# SFP_PortA-B.net
KiCad netlist of a schematic drawn in Altium Designer
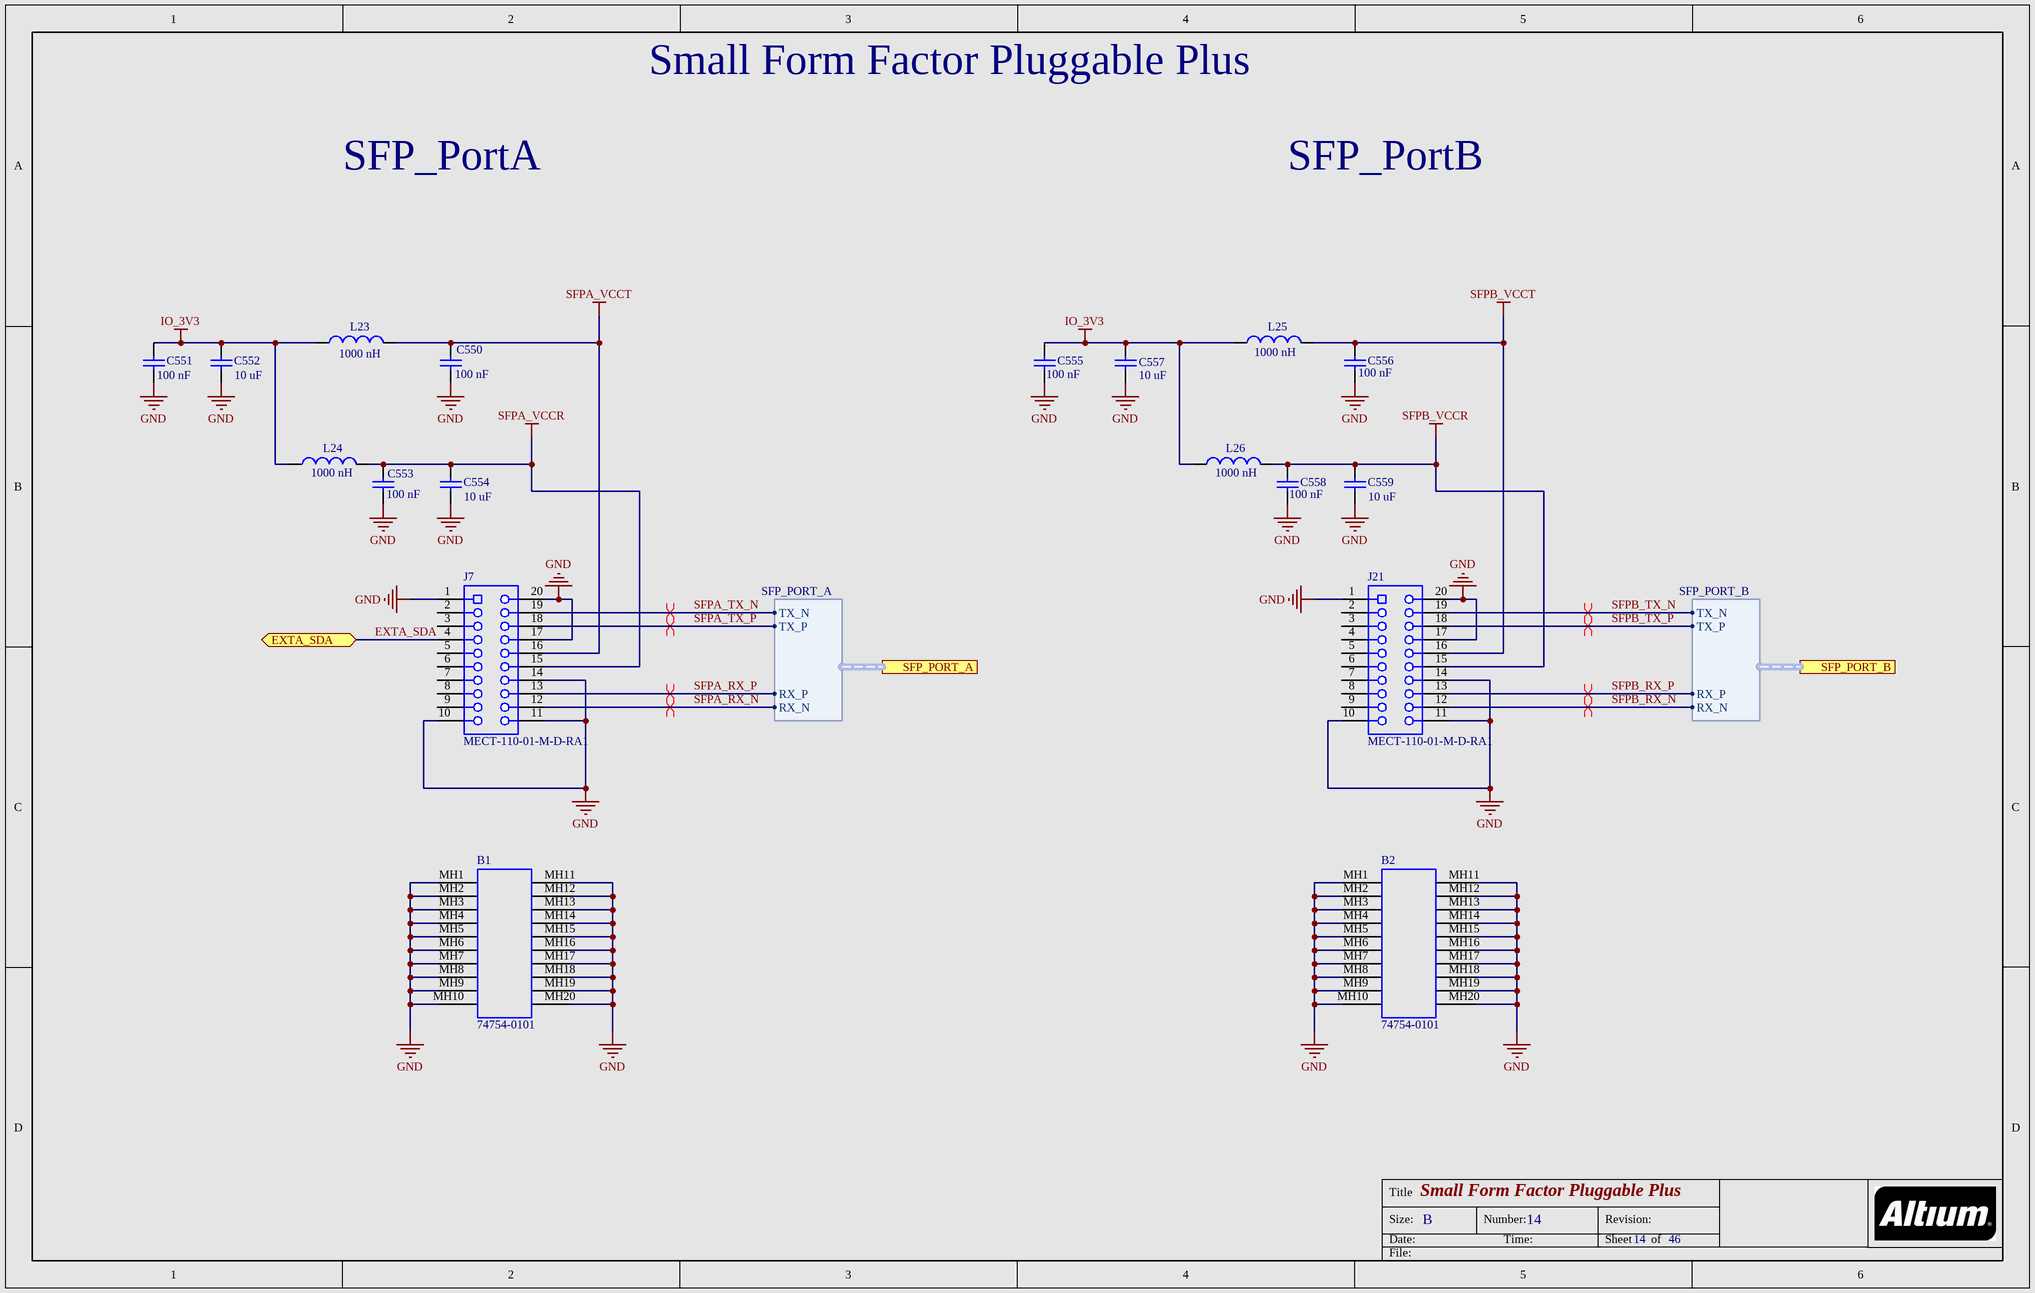
[diagram p0:  SFP_PortA-B.SchDoc]

(export (version "E")
  (design (tool "Eeschema 10.0.6"))
  (components
    (comp (ref "B1")
      (value "74754-0101")
      (footprint "MOLX-74754-0101_V")
      (description "SFP+ Cage, Single Port, Height 10.85 mm, Tail Height 3.05 mm, -40 to 85 degC, RoHS, Tray")
      (fields (field (name "MANUFACTURER") "Molex"))
      (libsource (lib "Altium Content Vault") (part "MOLX-74754-0101"))
    )
    (comp (ref "B2")
      (value "74754-0101")
      (footprint "MOLX-74754-0101_V")
      (description "SFP+ Cage, Single Port, Height 10.85 mm, Tail Height 3.05 mm, -40 to 85 degC, RoHS, Tray")
      (fields (field (name "MANUFACTURER") "Molex"))
      (libsource (lib "Altium Content Vault") (part "MOLX-74754-0101"))
    )
    (comp (ref "C550")
      (value "C1005X7R1E104M")
      (footprint "CAPC1005X55X10LL05")
      (description "Chip Capacitor, 0.1 uF, +/- 20%, 25 V, -55 to 125 degC, 0402 (1005 Metric), RoHS, Tape and Reel")
      (fields (field (name "TOLERANCE") "20%") (field (name "CAPACITANCE") "100 nF"))
      (libsource (lib "Altium Content Vault") (part "CAP-NP-2"))
    )
    (comp (ref "C551")
      (value "C1005X7R1E104M")
      (footprint "CAPC1005X55X10LL05")
      (description "Chip Capacitor, 0.1 uF, +/- 20%, 25 V, -55 to 125 degC, 0402 (1005 Metric), RoHS, Tape and Reel")
      (fields (field (name "TOLERANCE") "20%") (field (name "CAPACITANCE") "100 nF"))
      (libsource (lib "Altium Content Vault") (part "CAP-NP-2"))
    )
    (comp (ref "C552")
      (value "C2012X5R1C106K085AC")
      (footprint "CAPC2013X100X20NL20")
      (description "Chip Capacitor, 10 uF, +/- 10%, 16 V, -55 to 85 degC, 0805 (2012 Metric), RoHS, Tape and Reel")
      (fields (field (name "TOLERANCE") "10%") (field (name "CAPACITANCE") "10 uF"))
      (libsource (lib "Altium Content Vault") (part "CMP-1663-00007-1"))
    )
    (comp (ref "C553")
      (value "C1005X7R1E104M")
      (footprint "CAPC1005X55X10LL05")
      (description "Chip Capacitor, 0.1 uF, +/- 20%, 25 V, -55 to 125 degC, 0402 (1005 Metric), RoHS, Tape and Reel")
      (fields (field (name "TOLERANCE") "20%") (field (name "CAPACITANCE") "100 nF"))
      (libsource (lib "Altium Content Vault") (part "CAP-NP-2"))
    )
    (comp (ref "C554")
      (value "C2012X5R1C106K085AC")
      (footprint "CAPC2013X100X20NL20")
      (description "Chip Capacitor, 10 uF, +/- 10%, 16 V, -55 to 85 degC, 0805 (2012 Metric), RoHS, Tape and Reel")
      (fields (field (name "TOLERANCE") "10%") (field (name "CAPACITANCE") "10 uF"))
      (libsource (lib "Altium Content Vault") (part "CMP-1663-00007-1"))
    )
    (comp (ref "C555")
      (value "C1005X7R1E104M")
      (footprint "CAPC1005X55X10LL05")
      (description "Chip Capacitor, 0.1 uF, +/- 20%, 25 V, -55 to 125 degC, 0402 (1005 Metric), RoHS, Tape and Reel")
      (fields (field (name "TOLERANCE") "20%") (field (name "CAPACITANCE") "100 nF"))
      (libsource (lib "Altium Content Vault") (part "CAP-NP-2"))
    )
    (comp (ref "C556")
      (value "C1005X7R1E104M")
      (footprint "CAPC1005X55X10LL05")
      (description "Chip Capacitor, 0.1 uF, +/- 20%, 25 V, -55 to 125 degC, 0402 (1005 Metric), RoHS, Tape and Reel")
      (fields (field (name "TOLERANCE") "20%") (field (name "CAPACITANCE") "100 nF"))
      (libsource (lib "Altium Content Vault") (part "CAP-NP-2"))
    )
    (comp (ref "C557")
      (value "C2012X5R1C106K085AC")
      (footprint "CAPC2013X100X20NL20")
      (description "Chip Capacitor, 10 uF, +/- 10%, 16 V, -55 to 85 degC, 0805 (2012 Metric), RoHS, Tape and Reel")
      (fields (field (name "TOLERANCE") "10%") (field (name "CAPACITANCE") "10 uF"))
      (libsource (lib "") (part "CAP-NP-2_1"))
    )
    (comp (ref "C558")
      (value "C1005X7R1E104M")
      (footprint "CAPC1005X55X10LL05")
      (description "Chip Capacitor, 0.1 uF, +/- 20%, 25 V, -55 to 125 degC, 0402 (1005 Metric), RoHS, Tape and Reel")
      (fields (field (name "TOLERANCE") "20%") (field (name "CAPACITANCE") "100 nF"))
      (libsource (lib "Altium Content Vault") (part "CAP-NP-2"))
    )
    (comp (ref "C559")
      (value "C2012X5R1C106K085AC")
      (footprint "CAPC2013X100X20NL20")
      (description "Chip Capacitor, 10 uF, +/- 10%, 16 V, -55 to 85 degC, 0805 (2012 Metric), RoHS, Tape and Reel")
      (fields (field (name "TOLERANCE") "10%") (field (name "CAPACITANCE") "10 uF"))
      (libsource (lib "") (part "CAP-NP-2_1"))
    )
    (comp (ref "J7")
      (value "MECT-110-01-M-D-RA1")
      (footprint "SMTC-MECT-110-01-M-D-RA1_V")
      (fields (field (name "MANUFACTURER") "Samtec"))
      (libsource (lib "Altium Content Vault") (part "CMP-1707-00001-1"))
    )
    (comp (ref "J21")
      (value "MECT-110-01-M-D-RA1")
      (footprint "SMTC-MECT-110-01-M-D-RA1_V")
      (fields (field (name "MANUFACTURER") "Samtec"))
      (libsource (lib "Altium Content Vault") (part "CMP-1707-00001-1"))
    )
    (comp (ref "L23")
      (value "1008CS-102XFLC")
      (footprint "COIL-1008CS_V")
      (description "Chip Inductor, 1000 nH, +/- 1%, -40 to 125 degC, 2-Pin SMD, RoHS, Tape and Reel")
      (fields (field (name "INDUCTANCE") "1000 nH"))
      (libsource (lib "Altium Content Vault") (part "IND-2"))
    )
    (comp (ref "L24")
      (value "1008CS-102XFLC")
      (footprint "COIL-1008CS_V")
      (description "Chip Inductor, 1000 nH, +/- 1%, -40 to 125 degC, 2-Pin SMD, RoHS, Tape and Reel")
      (fields (field (name "INDUCTANCE") "1000 nH"))
      (libsource (lib "Altium Content Vault") (part "IND-2"))
    )
    (comp (ref "L25")
      (value "1008CS-102XFLC")
      (footprint "COIL-1008CS_V")
      (description "Chip Inductor, 1000 nH, +/- 1%, -40 to 125 degC, 2-Pin SMD, RoHS, Tape and Reel")
      (fields (field (name "INDUCTANCE") "1000 nH"))
      (libsource (lib "Altium Content Vault") (part "IND-2"))
    )
    (comp (ref "L26")
      (value "1008CS-102XFLC")
      (footprint "COIL-1008CS_V")
      (description "Chip Inductor, 1000 nH, +/- 1%, -40 to 125 degC, 2-Pin SMD, RoHS, Tape and Reel")
      (fields (field (name "INDUCTANCE") "1000 nH"))
      (libsource (lib "Altium Content Vault") (part "IND-2"))
    )
  )
  (nets
    (net (code "3") (name "/EXTA_SDA") (class "Default")
      (node (ref "J7") (pin "4") (pinfunction "4_4") (pintype "passive"))
    )
    (net (code "4") (name "/SFPA_RX_N") (class "Default")
      (node (ref "J7") (pin "12") (pinfunction "12_12") (pintype "passive"))
    )
    (net (code "5") (name "/SFPA_RX_P") (class "Default")
      (node (ref "J7") (pin "13") (pinfunction "13_13") (pintype "passive"))
    )
    (net (code "6") (name "/SFPA_TX_N") (class "Default")
      (node (ref "J7") (pin "19") (pinfunction "19_19") (pintype "passive"))
    )
    (net (code "7") (name "/SFPA_TX_P") (class "Default")
      (node (ref "J7") (pin "18") (pinfunction "18_18") (pintype "passive"))
    )
    (net (code "8") (name "/SFPB_RX_N") (class "Default")
      (node (ref "J21") (pin "12") (pinfunction "12_12") (pintype "passive"))
    )
    (net (code "9") (name "/SFPB_RX_P") (class "Default")
      (node (ref "J21") (pin "13") (pinfunction "13_13") (pintype "passive"))
    )
    (net (code "10") (name "/SFPB_TX_N") (class "Default")
      (node (ref "J21") (pin "19") (pinfunction "19_19") (pintype "passive"))
    )
    (net (code "11") (name "/SFPB_TX_P") (class "Default")
      (node (ref "J21") (pin "18") (pinfunction "18_18") (pintype "passive"))
    )
    (net (code "14") (name "GND") (class "Default")
      (node (ref "B1") (pin "MH1") (pinfunction "MH1_MH1") (pintype "passive"))
      (node (ref "B1") (pin "MH10") (pinfunction "MH10_MH10") (pintype "passive"))
      (node (ref "B1") (pin "MH11") (pinfunction "MH11_MH11") (pintype "passive"))
      (node (ref "B1") (pin "MH12") (pinfunction "MH12_MH12") (pintype "passive"))
      (node (ref "B1") (pin "MH13") (pinfunction "MH13_MH13") (pintype "passive"))
      (node (ref "B1") (pin "MH14") (pinfunction "MH14_MH14") (pintype "passive"))
      (node (ref "B1") (pin "MH15") (pinfunction "MH15_MH15") (pintype "passive"))
      (node (ref "B1") (pin "MH16") (pinfunction "MH16_MH16") (pintype "passive"))
      (node (ref "B1") (pin "MH17") (pinfunction "MH17_MH17") (pintype "passive"))
      (node (ref "B1") (pin "MH18") (pinfunction "MH18_MH18") (pintype "passive"))
      (node (ref "B1") (pin "MH19") (pinfunction "MH19_MH19") (pintype "passive"))
      (node (ref "B1") (pin "MH2") (pinfunction "MH2_MH2") (pintype "passive"))
      (node (ref "B1") (pin "MH20") (pinfunction "MH20_MH20") (pintype "passive"))
      (node (ref "B1") (pin "MH3") (pinfunction "MH3_MH3") (pintype "passive"))
      (node (ref "B1") (pin "MH4") (pinfunction "MH4_MH4") (pintype "passive"))
      (node (ref "B1") (pin "MH5") (pinfunction "MH5_MH5") (pintype "passive"))
      (node (ref "B1") (pin "MH6") (pinfunction "MH6_MH6") (pintype "passive"))
      (node (ref "B1") (pin "MH7") (pinfunction "MH7_MH7") (pintype "passive"))
      (node (ref "B1") (pin "MH8") (pinfunction "MH8_MH8") (pintype "passive"))
      (node (ref "B1") (pin "MH9") (pinfunction "MH9_MH9") (pintype "passive"))
      (node (ref "B2") (pin "MH1") (pinfunction "MH1_MH1") (pintype "passive"))
      (node (ref "B2") (pin "MH10") (pinfunction "MH10_MH10") (pintype "passive"))
      (node (ref "B2") (pin "MH11") (pinfunction "MH11_MH11") (pintype "passive"))
      (node (ref "B2") (pin "MH12") (pinfunction "MH12_MH12") (pintype "passive"))
      (node (ref "B2") (pin "MH13") (pinfunction "MH13_MH13") (pintype "passive"))
      (node (ref "B2") (pin "MH14") (pinfunction "MH14_MH14") (pintype "passive"))
      (node (ref "B2") (pin "MH15") (pinfunction "MH15_MH15") (pintype "passive"))
      (node (ref "B2") (pin "MH16") (pinfunction "MH16_MH16") (pintype "passive"))
      (node (ref "B2") (pin "MH17") (pinfunction "MH17_MH17") (pintype "passive"))
      (node (ref "B2") (pin "MH18") (pinfunction "MH18_MH18") (pintype "passive"))
      (node (ref "B2") (pin "MH19") (pinfunction "MH19_MH19") (pintype "passive"))
      (node (ref "B2") (pin "MH2") (pinfunction "MH2_MH2") (pintype "passive"))
      (node (ref "B2") (pin "MH20") (pinfunction "MH20_MH20") (pintype "passive"))
      (node (ref "B2") (pin "MH3") (pinfunction "MH3_MH3") (pintype "passive"))
      (node (ref "B2") (pin "MH4") (pinfunction "MH4_MH4") (pintype "passive"))
      (node (ref "B2") (pin "MH5") (pinfunction "MH5_MH5") (pintype "passive"))
      (node (ref "B2") (pin "MH6") (pinfunction "MH6_MH6") (pintype "passive"))
      (node (ref "B2") (pin "MH7") (pinfunction "MH7_MH7") (pintype "passive"))
      (node (ref "B2") (pin "MH8") (pinfunction "MH8_MH8") (pintype "passive"))
      (node (ref "B2") (pin "MH9") (pinfunction "MH9_MH9") (pintype "passive"))
      (node (ref "C550") (pin "1") (pinfunction "1_1") (pintype "passive"))
      (node (ref "C551") (pin "1") (pinfunction "1_1") (pintype "passive"))
      (node (ref "C552") (pin "1") (pinfunction "1_1") (pintype "passive"))
      (node (ref "C553") (pin "1") (pinfunction "1_1") (pintype "passive"))
      (node (ref "C554") (pin "1") (pinfunction "1_1") (pintype "passive"))
      (node (ref "C555") (pin "1") (pinfunction "1_1") (pintype "passive"))
      (node (ref "C556") (pin "1") (pinfunction "1_1") (pintype "passive"))
      (node (ref "C557") (pin "1") (pinfunction "1_1") (pintype "passive"))
      (node (ref "C558") (pin "1") (pinfunction "1_1") (pintype "passive"))
      (node (ref "C559") (pin "1") (pinfunction "1_1") (pintype "passive"))
      (node (ref "J21") (pin "1") (pinfunction "1_1") (pintype "passive"))
      (node (ref "J21") (pin "10") (pinfunction "10_10") (pintype "passive"))
      (node (ref "J21") (pin "11") (pinfunction "11_11") (pintype "passive"))
      (node (ref "J21") (pin "14") (pinfunction "14_14") (pintype "passive"))
      (node (ref "J21") (pin "17") (pinfunction "17_17") (pintype "passive"))
      (node (ref "J21") (pin "20") (pinfunction "20_20") (pintype "passive"))
      (node (ref "J7") (pin "1") (pinfunction "1_1") (pintype "passive"))
      (node (ref "J7") (pin "10") (pinfunction "10_10") (pintype "passive"))
      (node (ref "J7") (pin "11") (pinfunction "11_11") (pintype "passive"))
      (node (ref "J7") (pin "14") (pinfunction "14_14") (pintype "passive"))
      (node (ref "J7") (pin "17") (pinfunction "17_17") (pintype "passive"))
      (node (ref "J7") (pin "20") (pinfunction "20_20") (pintype "passive"))
    )
    (net (code "15") (name "IO_3V3") (class "Default")
      (node (ref "C551") (pin "2") (pinfunction "2_2") (pintype "passive"))
      (node (ref "C552") (pin "2") (pinfunction "2_2") (pintype "passive"))
      (node (ref "C555") (pin "2") (pinfunction "2_2") (pintype "passive"))
      (node (ref "C557") (pin "2") (pinfunction "2_2") (pintype "passive"))
      (node (ref "L23") (pin "1") (pinfunction "1_1") (pintype "passive"))
      (node (ref "L24") (pin "1") (pinfunction "1_1") (pintype "passive"))
      (node (ref "L25") (pin "1") (pinfunction "1_1") (pintype "passive"))
      (node (ref "L26") (pin "1") (pinfunction "1_1") (pintype "passive"))
    )
    (net (code "16") (name "SFPA_VCCR") (class "Default")
      (node (ref "C553") (pin "2") (pinfunction "2_2") (pintype "passive"))
      (node (ref "C554") (pin "2") (pinfunction "2_2") (pintype "passive"))
      (node (ref "J7") (pin "15") (pinfunction "15_15") (pintype "passive"))
      (node (ref "L24") (pin "2") (pinfunction "2_2") (pintype "passive"))
    )
    (net (code "17") (name "SFPA_VCCT") (class "Default")
      (node (ref "C550") (pin "2") (pinfunction "2_2") (pintype "passive"))
      (node (ref "J7") (pin "16") (pinfunction "16_16") (pintype "passive"))
      (node (ref "L23") (pin "2") (pinfunction "2_2") (pintype "passive"))
    )
    (net (code "18") (name "SFPB_VCCR") (class "Default")
      (node (ref "C558") (pin "2") (pinfunction "2_2") (pintype "passive"))
      (node (ref "C559") (pin "2") (pinfunction "2_2") (pintype "passive"))
      (node (ref "J21") (pin "15") (pinfunction "15_15") (pintype "passive"))
      (node (ref "L26") (pin "2") (pinfunction "2_2") (pintype "passive"))
    )
    (net (code "19") (name "SFPB_VCCT") (class "Default")
      (node (ref "C556") (pin "2") (pinfunction "2_2") (pintype "passive"))
      (node (ref "J21") (pin "16") (pinfunction "16_16") (pintype "passive"))
      (node (ref "L25") (pin "2") (pinfunction "2_2") (pintype "passive"))
    )
    (net (code "20") (name "unconnected-(J7-Pad2)") (class "Default")
      (node (ref "J7") (pin "2") (pinfunction "2_2") (pintype "passive"))
    )
    (net (code "21") (name "unconnected-(J7-Pad3)") (class "Default")
      (node (ref "J7") (pin "3") (pinfunction "3_3") (pintype "passive"))
    )
    (net (code "22") (name "unconnected-(J7-Pad5)") (class "Default")
      (node (ref "J7") (pin "5") (pinfunction "5_5") (pintype "passive"))
    )
    (net (code "23") (name "unconnected-(J7-Pad6)") (class "Default")
      (node (ref "J7") (pin "6") (pinfunction "6_6") (pintype "passive"))
    )
    (net (code "24") (name "unconnected-(J7-Pad7)") (class "Default")
      (node (ref "J7") (pin "7") (pinfunction "7_7") (pintype "passive"))
    )
    (net (code "25") (name "unconnected-(J7-Pad8)") (class "Default")
      (node (ref "J7") (pin "8") (pinfunction "8_8") (pintype "passive"))
    )
    (net (code "26") (name "unconnected-(J7-Pad9)") (class "Default")
      (node (ref "J7") (pin "9") (pinfunction "9_9") (pintype "passive"))
    )
    (net (code "27") (name "unconnected-(J21-Pad2)") (class "Default")
      (node (ref "J21") (pin "2") (pinfunction "2_2") (pintype "passive"))
    )
    (net (code "28") (name "unconnected-(J21-Pad3)") (class "Default")
      (node (ref "J21") (pin "3") (pinfunction "3_3") (pintype "passive"))
    )
    (net (code "29") (name "unconnected-(J21-Pad4)") (class "Default")
      (node (ref "J21") (pin "4") (pinfunction "4_4") (pintype "passive"))
    )
    (net (code "30") (name "unconnected-(J21-Pad5)") (class "Default")
      (node (ref "J21") (pin "5") (pinfunction "5_5") (pintype "passive"))
    )
    (net (code "31") (name "unconnected-(J21-Pad6)") (class "Default")
      (node (ref "J21") (pin "6") (pinfunction "6_6") (pintype "passive"))
    )
    (net (code "32") (name "unconnected-(J21-Pad7)") (class "Default")
      (node (ref "J21") (pin "7") (pinfunction "7_7") (pintype "passive"))
    )
    (net (code "33") (name "unconnected-(J21-Pad8)") (class "Default")
      (node (ref "J21") (pin "8") (pinfunction "8_8") (pintype "passive"))
    )
    (net (code "34") (name "unconnected-(J21-Pad9)") (class "Default")
      (node (ref "J21") (pin "9") (pinfunction "9_9") (pintype "passive"))
    )
  )
)
